# etch_a_sketch_schematic.net
KiCad netlist of a schematic drawn in EAGLE
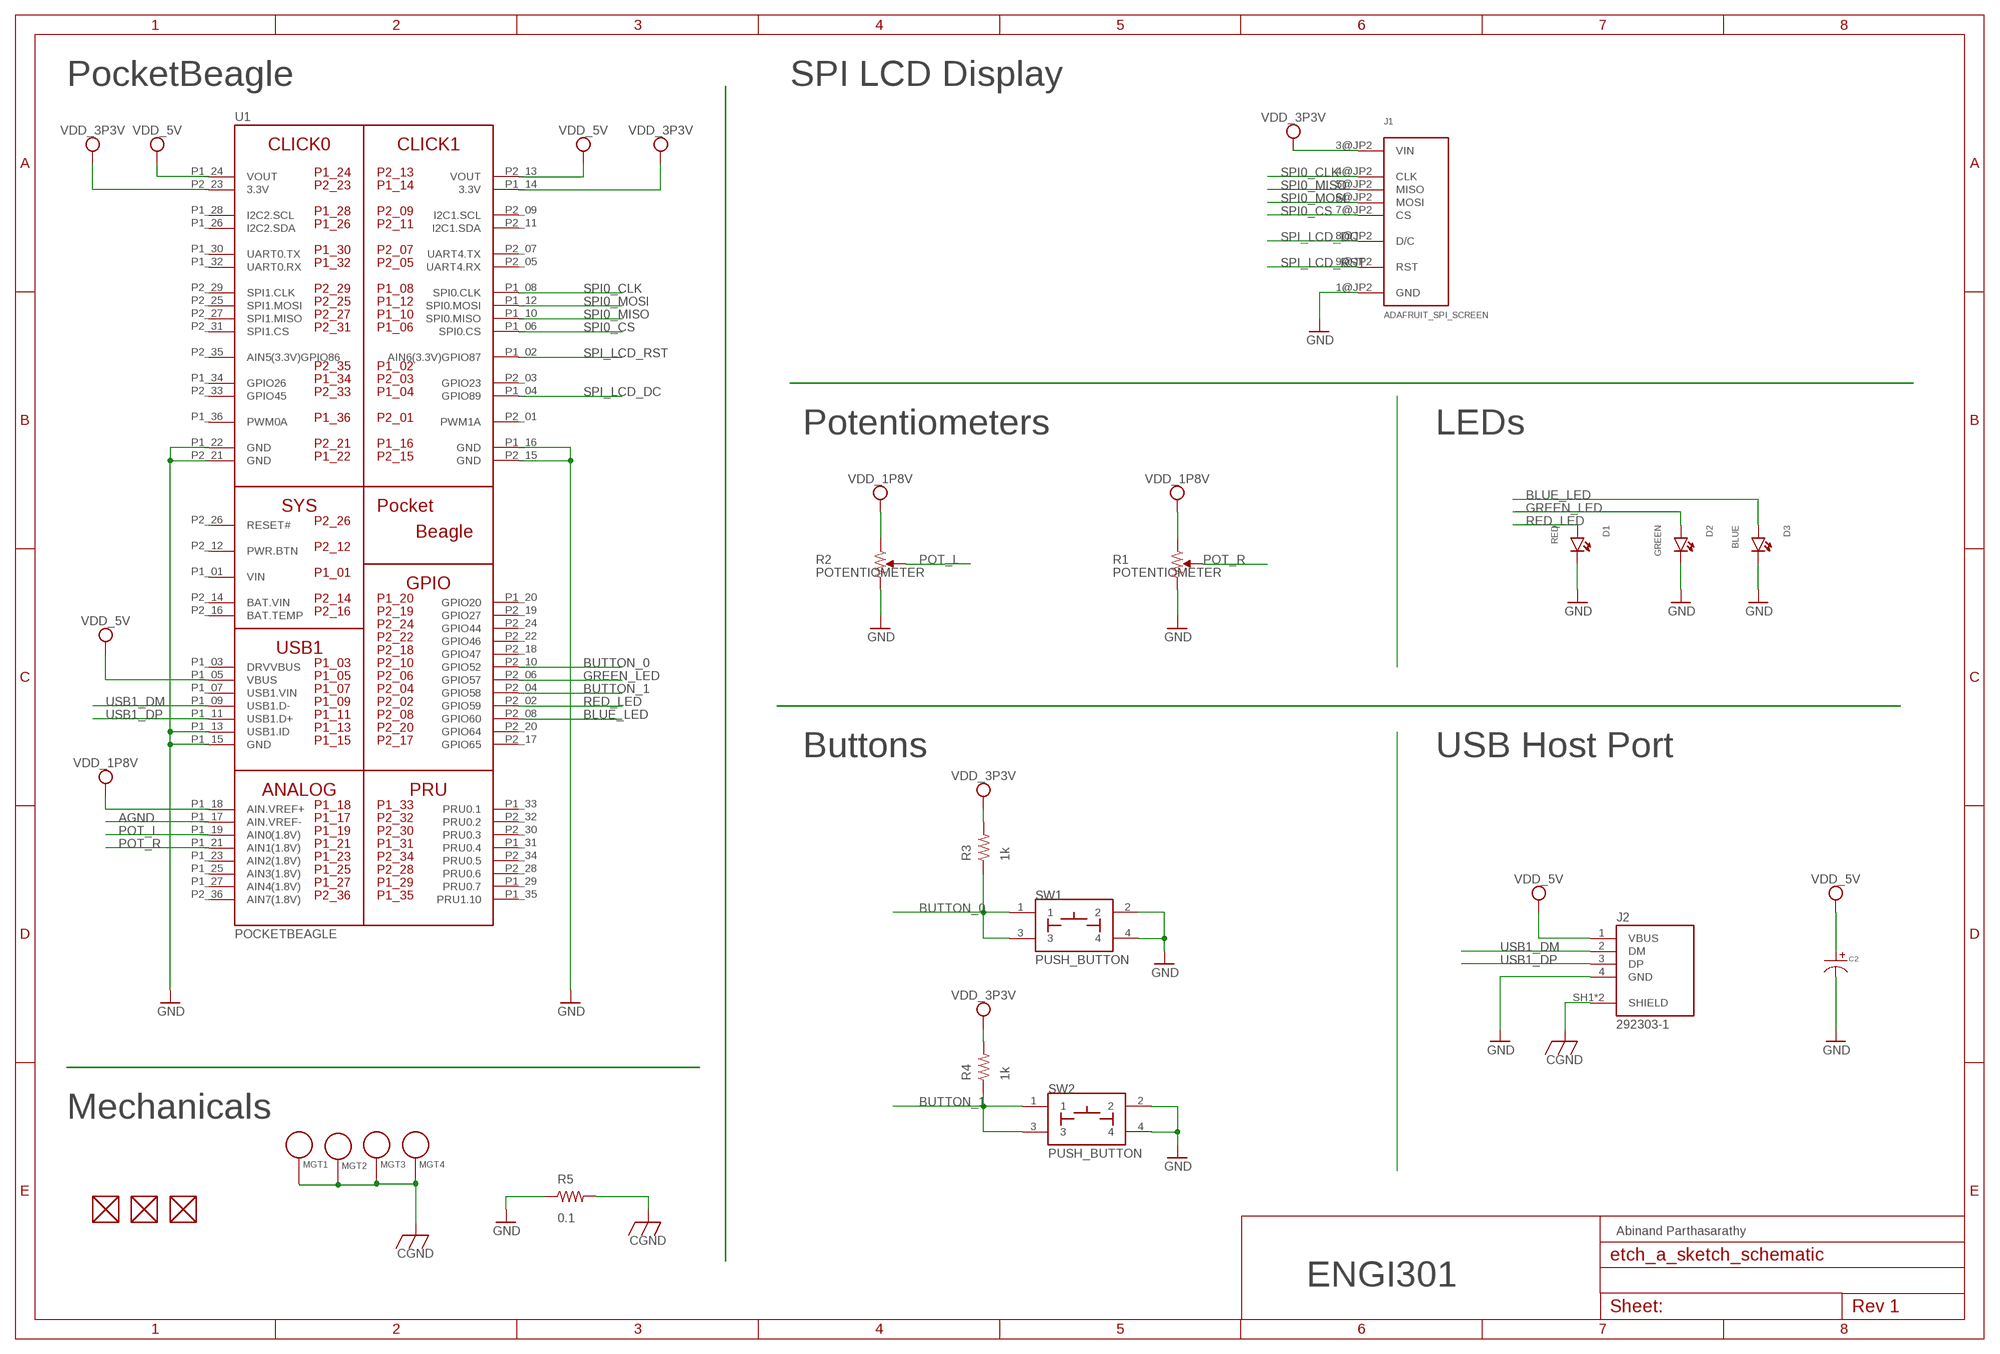
[diagram p0: schematic, sheet 1]

(export (version "E")
  (design (tool "Eeschema 10.0.6"))
  (components
    (comp (ref "C2")
      (value "CAPACITOR_P_10MM")
      (footprint "eagle-import:CP10MM")
      (libsource (lib "eagle-import") (part "CAPACITOR_P_10MM"))
    )
    (comp (ref "D1")
      (value "RED")
      (footprint "eagle-import:EIA-STD")
      (libsource (lib "eagle-import") (part "LED"))
    )
    (comp (ref "D2")
      (value "GREEN")
      (footprint "eagle-import:EIA-STD")
      (libsource (lib "eagle-import") (part "LED"))
    )
    (comp (ref "D3")
      (value "BLUE")
      (footprint "eagle-import:EIA-STD")
      (libsource (lib "eagle-import") (part "LED"))
    )
    (comp (ref "FUD2")
      (value "FIDUCIAL")
      (footprint "eagle-import:FIDUCIAL_40MIL")
      (libsource (lib "eagle-import") (part "FIDUCIAL"))
    )
    (comp (ref "FUD4")
      (value "FIDUCIAL")
      (footprint "eagle-import:FIDUCIAL_40MIL")
      (libsource (lib "eagle-import") (part "FIDUCIAL"))
    )
    (comp (ref "FUD6")
      (value "FIDUCIAL")
      (footprint "eagle-import:FIDUCIAL_40MIL")
      (libsource (lib "eagle-import") (part "FIDUCIAL"))
    )
    (comp (ref "J1")
      (value "ADAFRUIT_SPI_SCREEN")
      (footprint "eagle-import:ADAFRUIT_TFT_LCD_PCB")
      (libsource (lib "eagle-import") (part "ADAFRUIT_SPI_SCREEN"))
    )
    (comp (ref "J2")
      (value "292303-1")
      (footprint "eagle-import:TE_292303-1")
      (fields (field (name "MF") "TE Connectivity"))
      (libsource (lib "eagle-import") (part "292303-1"))
    )
    (comp (ref "MGT1")
      (value "MOUNTING_HOLE")
      (footprint "eagle-import:MOUNTING_HOLE")
      (libsource (lib "eagle-import") (part "MOUNTING_HOLE"))
    )
    (comp (ref "MGT2")
      (value "MOUNTING_HOLE")
      (footprint "eagle-import:MOUNTING_HOLE")
      (libsource (lib "eagle-import") (part "MOUNTING_HOLE"))
    )
    (comp (ref "MGT3")
      (value "MOUNTING_HOLE")
      (footprint "eagle-import:MOUNTING_HOLE")
      (libsource (lib "eagle-import") (part "MOUNTING_HOLE"))
    )
    (comp (ref "MGT4")
      (value "MOUNTING_HOLE")
      (footprint "eagle-import:MOUNTING_HOLE")
      (libsource (lib "eagle-import") (part "MOUNTING_HOLE"))
    )
    (comp (ref "R1")
      (value "POTENTIOMETER")
      (footprint "eagle-import:POT-PO90S")
      (libsource (lib "eagle-import") (part "POTENTIOMETER"))
    )
    (comp (ref "R2")
      (value "POTENTIOMETER")
      (footprint "eagle-import:POT-PO90S")
      (libsource (lib "eagle-import") (part "POTENTIOMETER"))
    )
    (comp (ref "R3")
      (value "1k")
      (footprint "eagle-import:R0603")
      (libsource (lib "eagle-import") (part "R_R0603"))
    )
    (comp (ref "R4")
      (value "1k")
      (footprint "eagle-import:R0603")
      (libsource (lib "eagle-import") (part "R_R0603"))
    )
    (comp (ref "R5")
      (value "0.1")
      (footprint "eagle-import:R0603")
      (libsource (lib "eagle-import") (part "R_R0603"))
    )
    (comp (ref "SW1")
      (value "PUSH_BUTTON")
      (footprint "eagle-import:BUTTON_12.5MM")
      (libsource (lib "eagle-import") (part "PUSH_BUTTON"))
    )
    (comp (ref "SW2")
      (value "PUSH_BUTTON")
      (footprint "eagle-import:BUTTON_12.5MM")
      (libsource (lib "eagle-import") (part "PUSH_BUTTON"))
    )
    (comp (ref "U1")
      (value "POCKETBEAGLE")
      (footprint "eagle-import:POCKETBEAGLE")
      (libsource (lib "eagle-import") (part "POCKETBEAGLE"))
    )
  )
  (nets
    (net (code "1") (name "/AGND") (class "Default")
      (node (ref "U1") (pin "P1_17") (pinfunction "AIN.VREF-_P1_17") (pintype "input"))
    )
    (net (code "2") (name "/BAT.VIN") (class "Default")
      (node (ref "U1") (pin "P2_14") (pinfunction "BAT.VIN_P2_14") (pintype "power_in"))
    )
    (net (code "3") (name "/BLUE_LED") (class "Default")
      (node (ref "D3") (pin "ANODE") (pinfunction "ANODE_ANODE") (pintype "bidirectional"))
      (node (ref "U1") (pin "P2_08") (pinfunction "GPIO60_P2_08") (pintype "bidirectional"))
    )
    (net (code "4") (name "/BUTTON_0") (class "Default")
      (node (ref "R3") (pin "1") (pinfunction "1_1") (pintype "passive"))
      (node (ref "SW1") (pin "1") (pinfunction "1_1") (pintype "bidirectional"))
      (node (ref "SW1") (pin "3") (pinfunction "3_3") (pintype "bidirectional"))
      (node (ref "U1") (pin "P2_10") (pinfunction "GPIO52_P2_10") (pintype "bidirectional"))
    )
    (net (code "5") (name "/BUTTON_1") (class "Default")
      (node (ref "R4") (pin "1") (pinfunction "1_1") (pintype "passive"))
      (node (ref "SW2") (pin "1") (pinfunction "1_1") (pintype "bidirectional"))
      (node (ref "SW2") (pin "3") (pinfunction "3_3") (pintype "bidirectional"))
      (node (ref "U1") (pin "P2_04") (pinfunction "GPIO58_P2_04") (pintype "bidirectional"))
    )
    (net (code "6") (name "/GREEN_LED") (class "Default")
      (node (ref "D2") (pin "ANODE") (pinfunction "ANODE_ANODE") (pintype "bidirectional"))
      (node (ref "U1") (pin "P2_06") (pinfunction "GPIO57_P2_06") (pintype "bidirectional"))
    )
    (net (code "8") (name "/POT_L") (class "Default")
      (node (ref "R2") (pin "S") (pinfunction "S_S") (pintype "bidirectional"))
      (node (ref "U1") (pin "P1_19") (pinfunction "AIN0(1.8V)_P1_19") (pintype "input"))
    )
    (net (code "9") (name "/POT_R") (class "Default")
      (node (ref "R1") (pin "S") (pinfunction "S_S") (pintype "bidirectional"))
      (node (ref "U1") (pin "P1_21") (pinfunction "AIN1(1.8V)_P1_21") (pintype "input"))
    )
    (net (code "10") (name "/RED_LED") (class "Default")
      (node (ref "D1") (pin "ANODE") (pinfunction "ANODE_ANODE") (pintype "bidirectional"))
      (node (ref "U1") (pin "P2_02") (pinfunction "GPIO59_P2_02") (pintype "bidirectional"))
    )
    (net (code "11") (name "/SPI0_CLK") (class "Default")
      (node (ref "J1") (pin "4@JP2") (pinfunction "CLK_4@JP2") (pintype "bidirectional"))
      (node (ref "U1") (pin "P1_08") (pinfunction "SPI0.CLK_P1_08") (pintype "bidirectional"))
    )
    (net (code "12") (name "/SPI0_CS") (class "Default")
      (node (ref "J1") (pin "7@JP2") (pinfunction "CS_7@JP2") (pintype "bidirectional"))
      (node (ref "U1") (pin "P1_06") (pinfunction "SPI0.CS_P1_06") (pintype "bidirectional"))
    )
    (net (code "13") (name "/SPI0_MISO") (class "Default")
      (node (ref "J1") (pin "5@JP2") (pinfunction "MISO_5@JP2") (pintype "bidirectional"))
      (node (ref "U1") (pin "P1_10") (pinfunction "SPI0.MISO_P1_10") (pintype "bidirectional"))
    )
    (net (code "14") (name "/SPI0_MOSI") (class "Default")
      (node (ref "J1") (pin "6@JP2") (pinfunction "MOSI_6@JP2") (pintype "bidirectional"))
      (node (ref "U1") (pin "P1_12") (pinfunction "SPI0.MOSI_P1_12") (pintype "bidirectional"))
    )
    (net (code "15") (name "/SPI_LCD_DC") (class "Default")
      (node (ref "J1") (pin "8@JP2") (pinfunction "D/C_8@JP2") (pintype "bidirectional"))
      (node (ref "U1") (pin "P1_04") (pinfunction "GPIO89_P1_04") (pintype "bidirectional"))
    )
    (net (code "16") (name "/SPI_LCD_RST") (class "Default")
      (node (ref "J1") (pin "9@JP2") (pinfunction "RST_9@JP2") (pintype "bidirectional"))
      (node (ref "U1") (pin "P1_02") (pinfunction "AIN6(3.3V)GPIO87_P1_02") (pintype "bidirectional"))
    )
    (net (code "17") (name "/USB1_DM") (class "Default")
      (node (ref "J2") (pin "2") (pinfunction "DM_2") (pintype "passive"))
      (node (ref "U1") (pin "P1_09") (pinfunction "USB1.D-_P1_09") (pintype "bidirectional"))
    )
    (net (code "18") (name "/USB1_DP") (class "Default")
      (node (ref "J2") (pin "3") (pinfunction "DP_3") (pintype "passive"))
      (node (ref "U1") (pin "P1_11") (pinfunction "USB1.D+_P1_11") (pintype "bidirectional"))
    )
    (net (code "19") (name "/VIN") (class "Default")
      (node (ref "U1") (pin "P1_01") (pinfunction "VIN_P1_01") (pintype "power_in"))
    )
    (net (code "20") (name "CGND") (class "Default")
      (node (ref "J2") (pin "SH1") (pinfunction "SHIELD_SH1") (pintype "passive"))
      (node (ref "J2") (pin "SH2") (pinfunction "SHIELD_SH2") (pintype "passive"))
      (node (ref "MGT1") (pin "P$1") (pinfunction "P$1_P$1") (pintype "bidirectional"))
      (node (ref "MGT2") (pin "P$1") (pinfunction "P$1_P$1") (pintype "bidirectional"))
      (node (ref "MGT3") (pin "P$1") (pinfunction "P$1_P$1") (pintype "bidirectional"))
      (node (ref "MGT4") (pin "P$1") (pinfunction "P$1_P$1") (pintype "bidirectional"))
      (node (ref "R5") (pin "2") (pinfunction "2_2") (pintype "passive"))
    )
    (net (code "21") (name "GND") (class "Default")
      (node (ref "C2") (pin "P$2") (pinfunction "P$2_P$2") (pintype "passive"))
      (node (ref "D1") (pin "CATHODE") (pinfunction "CATHODE_CATHODE") (pintype "bidirectional"))
      (node (ref "D2") (pin "CATHODE") (pinfunction "CATHODE_CATHODE") (pintype "bidirectional"))
      (node (ref "D3") (pin "CATHODE") (pinfunction "CATHODE_CATHODE") (pintype "bidirectional"))
      (node (ref "J1") (pin "1@JP2") (pinfunction "GND_1@JP2") (pintype "bidirectional"))
      (node (ref "J2") (pin "4") (pinfunction "GND_4") (pintype "passive"))
      (node (ref "R1") (pin "CW") (pinfunction "CW_CW") (pintype "passive"))
      (node (ref "R2") (pin "CW") (pinfunction "CW_CW") (pintype "passive"))
      (node (ref "R5") (pin "1") (pinfunction "1_1") (pintype "passive"))
      (node (ref "SW1") (pin "2") (pinfunction "2_2") (pintype "bidirectional"))
      (node (ref "SW1") (pin "4") (pinfunction "4_4") (pintype "bidirectional"))
      (node (ref "SW2") (pin "2") (pinfunction "2_2") (pintype "bidirectional"))
      (node (ref "SW2") (pin "4") (pinfunction "4_4") (pintype "bidirectional"))
      (node (ref "U1") (pin "P1_13") (pinfunction "USB1.ID_P1_13") (pintype "bidirectional"))
      (node (ref "U1") (pin "P1_15") (pinfunction "GND_P1_15") (pintype "bidirectional"))
      (node (ref "U1") (pin "P1_16") (pinfunction "GND_P1_16") (pintype "power_in"))
      (node (ref "U1") (pin "P1_22") (pinfunction "GND_P1_22") (pintype "power_in"))
      (node (ref "U1") (pin "P2_15") (pinfunction "GND_P2_15") (pintype "power_in"))
      (node (ref "U1") (pin "P2_21") (pinfunction "GND_P2_21") (pintype "power_in"))
    )
    (net (code "22") (name "VDD_1P8V") (class "Default")
      (node (ref "R1") (pin "CCW") (pinfunction "CCW_CCW") (pintype "passive"))
      (node (ref "R2") (pin "CCW") (pinfunction "CCW_CCW") (pintype "passive"))
      (node (ref "U1") (pin "P1_18") (pinfunction "AIN.VREF+_P1_18") (pintype "input"))
    )
    (net (code "23") (name "VDD_3P3V") (class "Default")
      (node (ref "J1") (pin "3@JP2") (pinfunction "VIN_3@JP2") (pintype "bidirectional"))
      (node (ref "R3") (pin "2") (pinfunction "2_2") (pintype "passive"))
      (node (ref "R4") (pin "2") (pinfunction "2_2") (pintype "passive"))
      (node (ref "U1") (pin "P1_14") (pinfunction "3.3V_P1_14") (pintype "power_in"))
      (node (ref "U1") (pin "P2_23") (pinfunction "3.3V_P2_23") (pintype "power_in"))
    )
    (net (code "24") (name "VDD_5V") (class "Default")
      (node (ref "C2") (pin "P$1") (pinfunction "P$1_P$1") (pintype "passive"))
      (node (ref "J2") (pin "1") (pinfunction "VBUS_1") (pintype "passive"))
      (node (ref "U1") (pin "P1_05") (pinfunction "VBUS_P1_05") (pintype "bidirectional"))
      (node (ref "U1") (pin "P1_24") (pinfunction "VOUT_P1_24") (pintype "power_in"))
      (node (ref "U1") (pin "P2_13") (pinfunction "VOUT_P2_13") (pintype "power_in"))
    )
    (net (code "25") (name "unconnected-(FUD2-PadP$1)") (class "Default")
      (node (ref "FUD2") (pin "P$1") (pinfunction "P$1_P$1") (pintype "no_connect"))
    )
    (net (code "26") (name "unconnected-(FUD4-PadP$1)") (class "Default")
      (node (ref "FUD4") (pin "P$1") (pinfunction "P$1_P$1") (pintype "no_connect"))
    )
    (net (code "27") (name "unconnected-(FUD6-PadP$1)") (class "Default")
      (node (ref "FUD6") (pin "P$1") (pinfunction "P$1_P$1") (pintype "no_connect"))
    )
    (net (code "28") (name "unconnected-(U1-AIN2(1.8V)-PadP1_23)") (class "Default")
      (node (ref "U1") (pin "P1_23") (pinfunction "AIN2(1.8V)_P1_23") (pintype "input"))
    )
    (net (code "29") (name "unconnected-(U1-AIN3(1.8V)-PadP1_25)") (class "Default")
      (node (ref "U1") (pin "P1_25") (pinfunction "AIN3(1.8V)_P1_25") (pintype "input"))
    )
    (net (code "30") (name "unconnected-(U1-AIN4(1.8V)-PadP1_27)") (class "Default")
      (node (ref "U1") (pin "P1_27") (pinfunction "AIN4(1.8V)_P1_27") (pintype "input"))
    )
    (net (code "31") (name "unconnected-(U1-AIN5(3.3V)GPIO86-PadP2_35)") (class "Default")
      (node (ref "U1") (pin "P2_35") (pinfunction "AIN5(3.3V)GPIO86_P2_35") (pintype "bidirectional"))
    )
    (net (code "32") (name "unconnected-(U1-AIN7(1.8V)-PadP2_36)") (class "Default")
      (node (ref "U1") (pin "P2_36") (pinfunction "AIN7(1.8V)_P2_36") (pintype "input"))
    )
    (net (code "33") (name "unconnected-(U1-BAT.TEMP-PadP2_16)") (class "Default")
      (node (ref "U1") (pin "P2_16") (pinfunction "BAT.TEMP_P2_16") (pintype "input"))
    )
    (net (code "34") (name "unconnected-(U1-DRVVBUS-PadP1_03)") (class "Default")
      (node (ref "U1") (pin "P1_03") (pinfunction "DRVVBUS_P1_03") (pintype "bidirectional"))
    )
    (net (code "35") (name "unconnected-(U1-GPIO20-PadP1_20)") (class "Default")
      (node (ref "U1") (pin "P1_20") (pinfunction "GPIO20_P1_20") (pintype "bidirectional"))
    )
    (net (code "36") (name "unconnected-(U1-GPIO23-PadP2_03)") (class "Default")
      (node (ref "U1") (pin "P2_03") (pinfunction "GPIO23_P2_03") (pintype "bidirectional"))
    )
    (net (code "37") (name "unconnected-(U1-GPIO26-PadP1_34)") (class "Default")
      (node (ref "U1") (pin "P1_34") (pinfunction "GPIO26_P1_34") (pintype "bidirectional"))
    )
    (net (code "38") (name "unconnected-(U1-GPIO27-PadP2_19)") (class "Default")
      (node (ref "U1") (pin "P2_19") (pinfunction "GPIO27_P2_19") (pintype "bidirectional"))
    )
    (net (code "39") (name "unconnected-(U1-GPIO44-PadP2_24)") (class "Default")
      (node (ref "U1") (pin "P2_24") (pinfunction "GPIO44_P2_24") (pintype "bidirectional"))
    )
    (net (code "40") (name "unconnected-(U1-GPIO45-PadP2_33)") (class "Default")
      (node (ref "U1") (pin "P2_33") (pinfunction "GPIO45_P2_33") (pintype "bidirectional"))
    )
    (net (code "41") (name "unconnected-(U1-GPIO46-PadP2_22)") (class "Default")
      (node (ref "U1") (pin "P2_22") (pinfunction "GPIO46_P2_22") (pintype "bidirectional"))
    )
    (net (code "42") (name "unconnected-(U1-GPIO47-PadP2_18)") (class "Default")
      (node (ref "U1") (pin "P2_18") (pinfunction "GPIO47_P2_18") (pintype "bidirectional"))
    )
    (net (code "43") (name "unconnected-(U1-GPIO64-PadP2_20)") (class "Default")
      (node (ref "U1") (pin "P2_20") (pinfunction "GPIO64_P2_20") (pintype "bidirectional"))
    )
    (net (code "44") (name "unconnected-(U1-GPIO65-PadP2_17)") (class "Default")
      (node (ref "U1") (pin "P2_17") (pinfunction "GPIO65_P2_17") (pintype "bidirectional"))
    )
    (net (code "45") (name "unconnected-(U1-I2C1.SCL-PadP2_09)") (class "Default")
      (node (ref "U1") (pin "P2_09") (pinfunction "I2C1.SCL_P2_09") (pintype "bidirectional"))
    )
    (net (code "46") (name "unconnected-(U1-I2C1.SDA-PadP2_11)") (class "Default")
      (node (ref "U1") (pin "P2_11") (pinfunction "I2C1.SDA_P2_11") (pintype "bidirectional"))
    )
    (net (code "47") (name "unconnected-(U1-I2C2.SCL-PadP1_28)") (class "Default")
      (node (ref "U1") (pin "P1_28") (pinfunction "I2C2.SCL_P1_28") (pintype "bidirectional"))
    )
    (net (code "48") (name "unconnected-(U1-I2C2.SDA-PadP1_26)") (class "Default")
      (node (ref "U1") (pin "P1_26") (pinfunction "I2C2.SDA_P1_26") (pintype "bidirectional"))
    )
    (net (code "49") (name "unconnected-(U1-PRU0.1-PadP1_33)") (class "Default")
      (node (ref "U1") (pin "P1_33") (pinfunction "PRU0.1_P1_33") (pintype "bidirectional"))
    )
    (net (code "50") (name "unconnected-(U1-PRU0.2-PadP2_32)") (class "Default")
      (node (ref "U1") (pin "P2_32") (pinfunction "PRU0.2_P2_32") (pintype "bidirectional"))
    )
    (net (code "51") (name "unconnected-(U1-PRU0.3-PadP2_30)") (class "Default")
      (node (ref "U1") (pin "P2_30") (pinfunction "PRU0.3_P2_30") (pintype "bidirectional"))
    )
    (net (code "52") (name "unconnected-(U1-PRU0.4-PadP1_31)") (class "Default")
      (node (ref "U1") (pin "P1_31") (pinfunction "PRU0.4_P1_31") (pintype "bidirectional"))
    )
    (net (code "53") (name "unconnected-(U1-PRU0.5-PadP2_34)") (class "Default")
      (node (ref "U1") (pin "P2_34") (pinfunction "PRU0.5_P2_34") (pintype "bidirectional"))
    )
    (net (code "54") (name "unconnected-(U1-PRU0.6-PadP2_28)") (class "Default")
      (node (ref "U1") (pin "P2_28") (pinfunction "PRU0.6_P2_28") (pintype "bidirectional"))
    )
    (net (code "55") (name "unconnected-(U1-PRU0.7-PadP1_29)") (class "Default")
      (node (ref "U1") (pin "P1_29") (pinfunction "PRU0.7_P1_29") (pintype "bidirectional"))
    )
    (net (code "56") (name "unconnected-(U1-PRU1.10-PadP1_35)") (class "Default")
      (node (ref "U1") (pin "P1_35") (pinfunction "PRU1.10_P1_35") (pintype "bidirectional"))
    )
    (net (code "57") (name "unconnected-(U1-PWM0A-PadP1_36)") (class "Default")
      (node (ref "U1") (pin "P1_36") (pinfunction "PWM0A_P1_36") (pintype "bidirectional"))
    )
    (net (code "58") (name "unconnected-(U1-PWM1A-PadP2_01)") (class "Default")
      (node (ref "U1") (pin "P2_01") (pinfunction "PWM1A_P2_01") (pintype "bidirectional"))
    )
    (net (code "59") (name "unconnected-(U1-PWR.BTN-PadP2_12)") (class "Default")
      (node (ref "U1") (pin "P2_12") (pinfunction "PWR.BTN_P2_12") (pintype "input"))
    )
    (net (code "60") (name "unconnected-(U1-RESET#-PadP2_26)") (class "Default")
      (node (ref "U1") (pin "P2_26") (pinfunction "RESET#_P2_26") (pintype "input"))
    )
    (net (code "61") (name "unconnected-(U1-SPI1.CLK-PadP2_29)") (class "Default")
      (node (ref "U1") (pin "P2_29") (pinfunction "SPI1.CLK_P2_29") (pintype "bidirectional"))
    )
    (net (code "62") (name "unconnected-(U1-SPI1.CS-PadP2_31)") (class "Default")
      (node (ref "U1") (pin "P2_31") (pinfunction "SPI1.CS_P2_31") (pintype "bidirectional"))
    )
    (net (code "63") (name "unconnected-(U1-SPI1.MISO-PadP2_27)") (class "Default")
      (node (ref "U1") (pin "P2_27") (pinfunction "SPI1.MISO_P2_27") (pintype "bidirectional"))
    )
    (net (code "64") (name "unconnected-(U1-SPI1.MOSI-PadP2_25)") (class "Default")
      (node (ref "U1") (pin "P2_25") (pinfunction "SPI1.MOSI_P2_25") (pintype "bidirectional"))
    )
    (net (code "65") (name "unconnected-(U1-UART0.RX-PadP1_32)") (class "Default")
      (node (ref "U1") (pin "P1_32") (pinfunction "UART0.RX_P1_32") (pintype "bidirectional"))
    )
    (net (code "66") (name "unconnected-(U1-UART0.TX-PadP1_30)") (class "Default")
      (node (ref "U1") (pin "P1_30") (pinfunction "UART0.TX_P1_30") (pintype "bidirectional"))
    )
    (net (code "67") (name "unconnected-(U1-UART4.RX-PadP2_05)") (class "Default")
      (node (ref "U1") (pin "P2_05") (pinfunction "UART4.RX_P2_05") (pintype "bidirectional"))
    )
    (net (code "68") (name "unconnected-(U1-UART4.TX-PadP2_07)") (class "Default")
      (node (ref "U1") (pin "P2_07") (pinfunction "UART4.TX_P2_07") (pintype "bidirectional"))
    )
    (net (code "69") (name "unconnected-(U1-USB1.VIN-PadP1_07)") (class "Default")
      (node (ref "U1") (pin "P1_07") (pinfunction "USB1.VIN_P1_07") (pintype "bidirectional"))
    )
  )
)
